# untitled.net
KiCad netlist of a schematic drawn in EAGLE
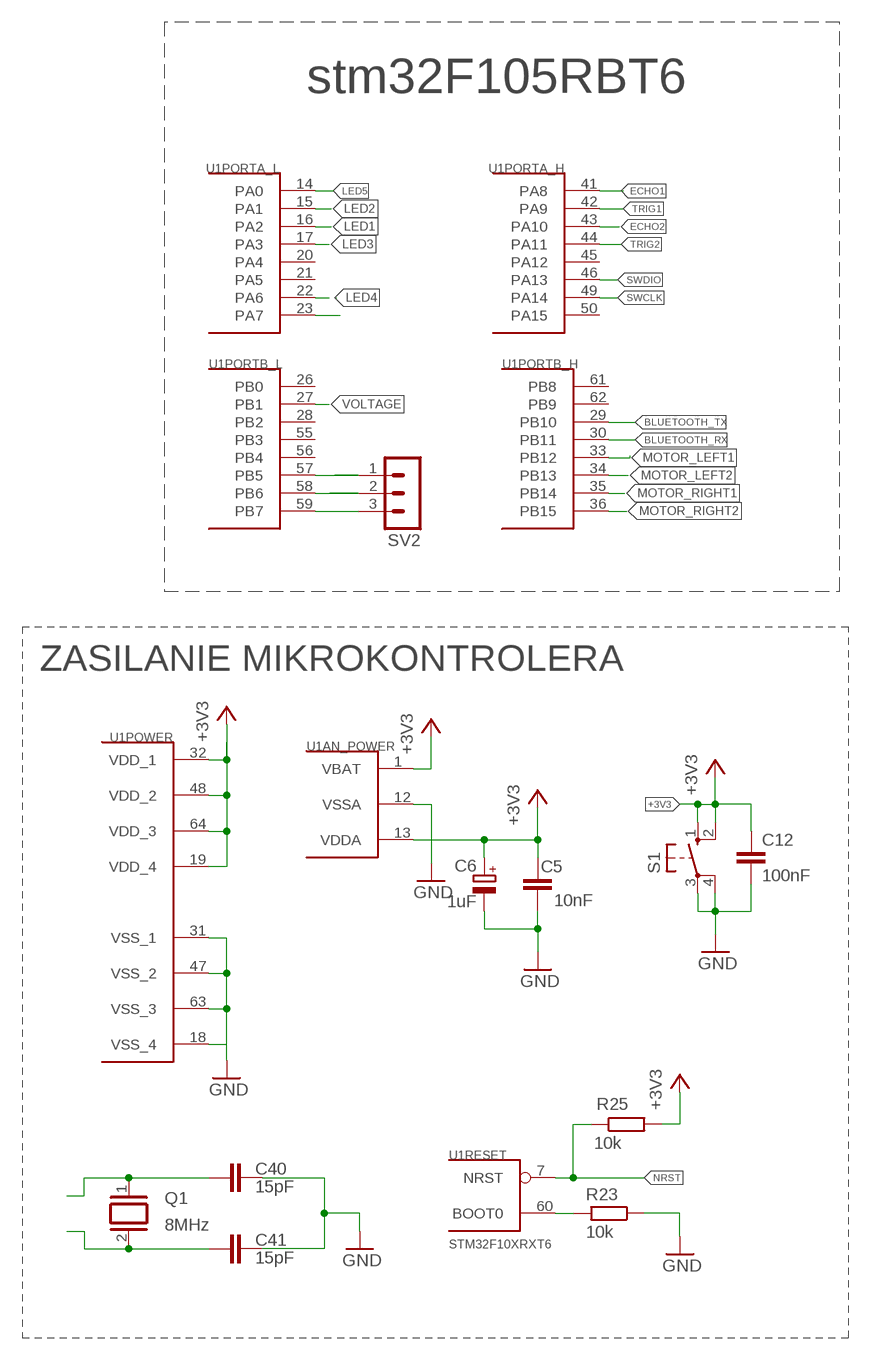
[diagram p0: schematic, sheet 1, part 1 of 2]
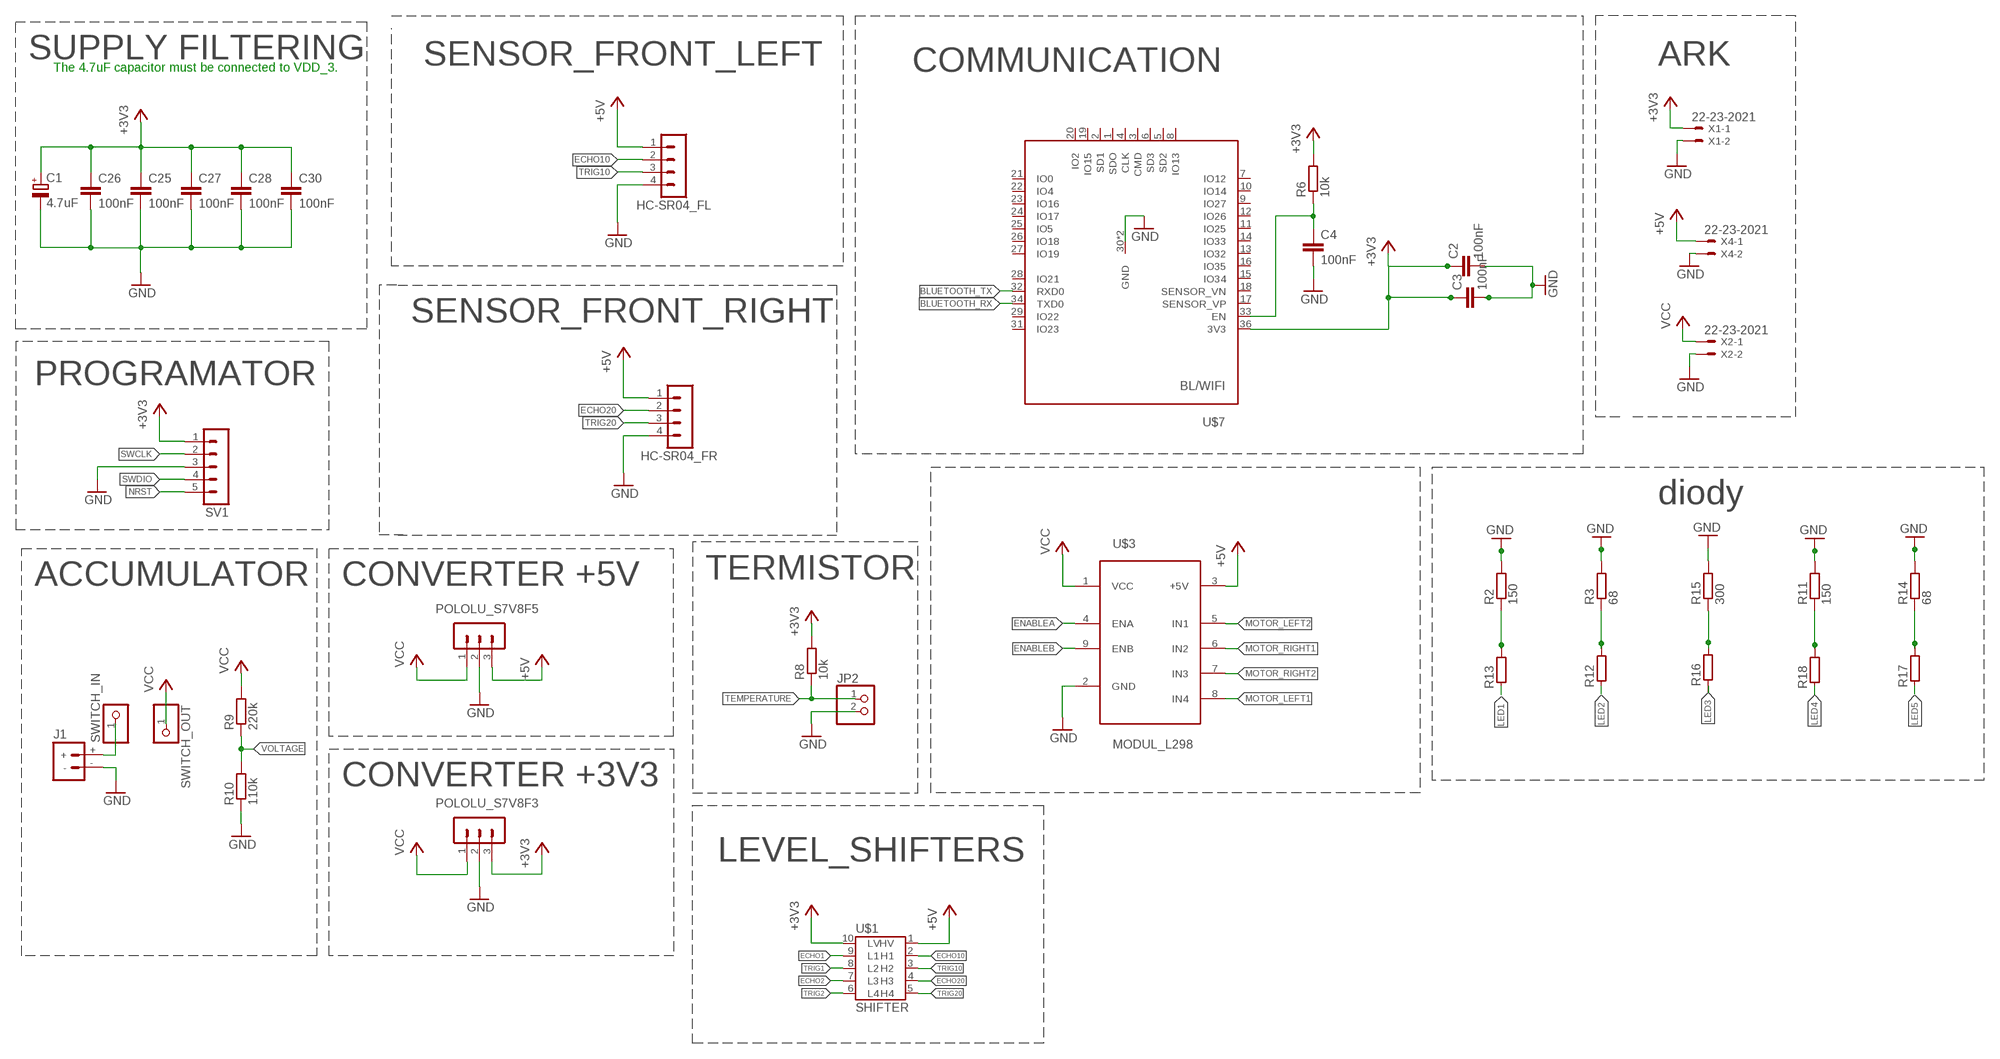
[diagram p1: schematic, sheet 1, part 2 of 2]

(export (version "E")
  (design (tool "Eeschema 10.0.6"))
  (components
    (comp (ref "C1")
      (value "4.7uF")
      (footprint "eagle-import:A_3216-18R")
      (libsource (lib "eagle-import") (part "CPOL-EUA/3216-18R"))
    )
    (comp (ref "C2")
      (value "100nF")
      (footprint "eagle-import:C0805")
      (libsource (lib "eagle-import") (part "C-EUC0805"))
    )
    (comp (ref "C3")
      (value "100nF")
      (footprint "eagle-import:C0805")
      (libsource (lib "eagle-import") (part "C-EUC0805"))
    )
    (comp (ref "C4")
      (value "100nF")
      (footprint "eagle-import:C0805")
      (libsource (lib "eagle-import") (part "C-EUC0805"))
    )
    (comp (ref "C5")
      (value "10nF")
      (footprint "eagle-import:C0805")
      (libsource (lib "eagle-import") (part "C-EUC0805"))
    )
    (comp (ref "C6")
      (value "1uF")
      (footprint "eagle-import:B_3528-21W")
      (libsource (lib "eagle-import") (part "CPOL-EUB/3528-21W"))
    )
    (comp (ref "C12")
      (value "100nF")
      (footprint "eagle-import:C0805")
      (libsource (lib "eagle-import") (part "C-EUC0805"))
    )
    (comp (ref "C25")
      (value "100nF")
      (footprint "eagle-import:C0805")
      (libsource (lib "eagle-import") (part "C-EUC0805"))
    )
    (comp (ref "C26")
      (value "100nF")
      (footprint "eagle-import:C0805")
      (libsource (lib "eagle-import") (part "C-EUC0805"))
    )
    (comp (ref "C27")
      (value "100nF")
      (footprint "eagle-import:C0805")
      (libsource (lib "eagle-import") (part "C-EUC0805"))
    )
    (comp (ref "C28")
      (value "100nF")
      (footprint "eagle-import:C0805")
      (libsource (lib "eagle-import") (part "C-EUC0805"))
    )
    (comp (ref "C30")
      (value "100nF")
      (footprint "eagle-import:C0805")
      (libsource (lib "eagle-import") (part "C-EUC0805"))
    )
    (comp (ref "C40")
      (value "15pF")
      (footprint "eagle-import:C0805")
      (libsource (lib "eagle-import") (part "C-EUC0805"))
    )
    (comp (ref "C41")
      (value "15pF")
      (footprint "eagle-import:C0805")
      (libsource (lib "eagle-import") (part "C-EUC0805"))
    )
    (comp (ref "HC-SR04_FL")
      (value "MA04-1")
      (footprint "eagle-import:MA04-1")
      (libsource (lib "eagle-import") (part "MA04-1"))
    )
    (comp (ref "HC-SR04_FR")
      (value "MA04-1")
      (footprint "eagle-import:MA04-1")
      (libsource (lib "eagle-import") (part "MA04-1"))
    )
    (comp (ref "J1")
      (value "BATTERY_CONN_DEANS")
      (footprint "eagle-import:DEANS")
      (libsource (lib "eagle-import") (part "BATTERY_CONN_DEANS"))
    )
    (comp (ref "JP2")
      (value "PINHD-1X2")
      (footprint "eagle-import:1X02")
      (libsource (lib "eagle-import") (part "PINHD-1X2"))
    )
    (comp (ref "POLOLU_S7V8F3")
      (value "MA03-1")
      (footprint "eagle-import:MA03-1")
      (libsource (lib "eagle-import") (part "MA03-1"))
    )
    (comp (ref "POLOLU_S7V8F5")
      (value "MA03-1")
      (footprint "eagle-import:MA03-1")
      (libsource (lib "eagle-import") (part "MA03-1"))
    )
    (comp (ref "Q1")
      (value "8MHz")
      (footprint "eagle-import:Q")
      (libsource (lib "eagle-import") (part "XTAL"))
    )
    (comp (ref "R2")
      (value "150")
      (footprint "eagle-import:R0805")
      (libsource (lib "eagle-import") (part "R-EU_R0805"))
    )
    (comp (ref "R3")
      (value "68")
      (footprint "eagle-import:M0805")
      (libsource (lib "eagle-import") (part "resistor_348_R-EU_M0805"))
    )
    (comp (ref "R6")
      (value "10k")
      (footprint "eagle-import:M0805")
      (libsource (lib "eagle-import") (part "resistor_348_R-EU_M0805"))
    )
    (comp (ref "R8")
      (value "10k")
      (footprint "eagle-import:R0805")
      (libsource (lib "eagle-import") (part "R-EU_R0805"))
    )
    (comp (ref "R9")
      (value "220k")
      (footprint "eagle-import:R0805")
      (libsource (lib "eagle-import") (part "R-EU_R0805"))
    )
    (comp (ref "R10")
      (value "110k")
      (footprint "eagle-import:R0805")
      (libsource (lib "eagle-import") (part "R-EU_R0805"))
    )
    (comp (ref "R11")
      (value "150")
      (footprint "eagle-import:R0805")
      (libsource (lib "eagle-import") (part "R-EU_R0805"))
    )
    (comp (ref "R12")
      (value "R-EU_0204/5")
      (footprint "eagle-import:0204_5")
      (libsource (lib "eagle-import") (part "R-EU_0204/5"))
    )
    (comp (ref "R13")
      (value "R-EU_0204/5")
      (footprint "eagle-import:0204_5")
      (libsource (lib "eagle-import") (part "R-EU_0204/5"))
    )
    (comp (ref "R14")
      (value "68")
      (footprint "eagle-import:M0805")
      (libsource (lib "eagle-import") (part "resistor_348_R-EU_M0805"))
    )
    (comp (ref "R15")
      (value "300")
      (footprint "eagle-import:R0805")
      (libsource (lib "eagle-import") (part "R-EU_R0805"))
    )
    (comp (ref "R16")
      (value "R-EU_0204/5")
      (footprint "eagle-import:0204_5")
      (libsource (lib "eagle-import") (part "R-EU_0204/5"))
    )
    (comp (ref "R17")
      (value "R-EU_0204/5")
      (footprint "eagle-import:0204_5")
      (libsource (lib "eagle-import") (part "R-EU_0204/5"))
    )
    (comp (ref "R18")
      (value "R-EU_0204/5")
      (footprint "eagle-import:0204_5")
      (libsource (lib "eagle-import") (part "R-EU_0204/5"))
    )
    (comp (ref "R23")
      (value "10k")
      (footprint "eagle-import:R0805")
      (libsource (lib "eagle-import") (part "R-EU_R0805"))
    )
    (comp (ref "R25")
      (value "10k")
      (footprint "eagle-import:R0805")
      (libsource (lib "eagle-import") (part "R-EU_R0805"))
    )
    (comp (ref "S1")
      (value "TACT_SWITCH")
      (footprint "eagle-import:B3F-10XX")
      (libsource (lib "eagle-import") (part "TACT_SWITCH"))
    )
    (comp (ref "SV1")
      (value "MA05-1")
      (footprint "eagle-import:MA05-1")
      (libsource (lib "eagle-import") (part "MA05-1"))
    )
    (comp (ref "SV2")
      (value "MA03-1")
      (footprint "eagle-import:MA03-1")
      (libsource (lib "eagle-import") (part "MA03-1"))
    )
    (comp (ref "SWITCH_IN")
      (value "PINHD-1X1")
      (footprint "eagle-import:1X01")
      (libsource (lib "eagle-import") (part "PINHD-1X1"))
    )
    (comp (ref "SWITCH_OUT")
      (value "PINHD-1X1")
      (footprint "eagle-import:1X01")
      (libsource (lib "eagle-import") (part "PINHD-1X1"))
    )
    (comp (ref "U$1")
      (value "SHIFTER")
      (footprint "eagle-import:SHIFTER")
      (libsource (lib "eagle-import") (part "SHIFTER"))
    )
    (comp (ref "U$3")
      (value "MODUL_L298")
      (footprint "eagle-import:MODUL_L298")
      (libsource (lib "eagle-import") (part "MODUL_L298"))
    )
    (comp (ref "U$7")
      (value "BL/WIFI")
      (footprint "eagle-import:BL_WIFI")
      (libsource (lib "eagle-import") (part "BL/WIFI"))
    )
    (comp (ref "U1")
      (value "STM32F10XRXT6")
      (footprint "eagle-import:TQFP64")
      (libsource (lib "eagle-import") (part "STM32F10XRXT6"))
    )
    (comp (ref "X1")
      (value "22-23-2021")
      (footprint "eagle-import:22-23-2021")
      (fields (field (name "MF") "MOLEX"))
      (libsource (lib "eagle-import") (part "22-23-2021"))
    )
    (comp (ref "X2")
      (value "22-23-2021")
      (footprint "eagle-import:22-23-2021")
      (fields (field (name "MF") "MOLEX"))
      (libsource (lib "eagle-import") (part "22-23-2021"))
    )
    (comp (ref "X4")
      (value "22-23-2021")
      (footprint "eagle-import:22-23-2021")
      (fields (field (name "MF") "MOLEX"))
      (libsource (lib "eagle-import") (part "22-23-2021"))
    )
  )
  (nets
    (net (code "1") (name "+3V3") (class "Default")
      (node (ref "C1") (pin "+") (pinfunction "+_+") (pintype "passive"))
      (node (ref "C12") (pin "1") (pinfunction "1_1") (pintype "passive"))
      (node (ref "C2") (pin "1") (pinfunction "1_1") (pintype "passive"))
      (node (ref "C25") (pin "1") (pinfunction "1_1") (pintype "passive"))
      (node (ref "C26") (pin "1") (pinfunction "1_1") (pintype "passive"))
      (node (ref "C27") (pin "1") (pinfunction "1_1") (pintype "passive"))
      (node (ref "C28") (pin "1") (pinfunction "1_1") (pintype "passive"))
      (node (ref "C3") (pin "1") (pinfunction "1_1") (pintype "passive"))
      (node (ref "C30") (pin "1") (pinfunction "1_1") (pintype "passive"))
      (node (ref "C5") (pin "2") (pinfunction "2_2") (pintype "passive"))
      (node (ref "C6") (pin "+") (pinfunction "+_+") (pintype "passive"))
      (node (ref "POLOLU_S7V8F3") (pin "3") (pinfunction "3_3") (pintype "passive"))
      (node (ref "R25") (pin "2") (pinfunction "2_2") (pintype "passive"))
      (node (ref "R6") (pin "2") (pinfunction "2_2") (pintype "passive"))
      (node (ref "R8") (pin "2") (pinfunction "2_2") (pintype "passive"))
      (node (ref "S1") (pin "1") (pinfunction "S_1") (pintype "passive"))
      (node (ref "S1") (pin "2") (pinfunction "S1_2") (pintype "passive"))
      (node (ref "SV1") (pin "1") (pinfunction "1_1") (pintype "passive"))
      (node (ref "U$1") (pin "10") (pinfunction "LV_10") (pintype "bidirectional"))
      (node (ref "U$7") (pin "36") (pinfunction "3V3_36") (pintype "bidirectional"))
      (node (ref "U1") (pin "1") (pinfunction "VBAT_1") (pintype "power_in"))
      (node (ref "U1") (pin "13") (pinfunction "VDDA_13") (pintype "power_in"))
      (node (ref "U1") (pin "19") (pinfunction "VDD_4_19") (pintype "power_in"))
      (node (ref "U1") (pin "32") (pinfunction "VDD_1_32") (pintype "power_in"))
      (node (ref "U1") (pin "48") (pinfunction "VDD_2_48") (pintype "power_in"))
      (node (ref "U1") (pin "64") (pinfunction "VDD_3_64") (pintype "power_in"))
      (node (ref "X1") (pin "1") (pinfunction "S_1") (pintype "passive"))
    )
    (net (code "2") (name "+5V") (class "Default")
      (node (ref "HC-SR04_FL") (pin "1") (pinfunction "1_1") (pintype "passive"))
      (node (ref "HC-SR04_FR") (pin "1") (pinfunction "1_1") (pintype "passive"))
      (node (ref "POLOLU_S7V8F5") (pin "3") (pinfunction "3_3") (pintype "passive"))
      (node (ref "U$1") (pin "1") (pinfunction "HV_1") (pintype "bidirectional"))
      (node (ref "U$3") (pin "3") (pinfunction "+5V_3") (pintype "bidirectional"))
      (node (ref "X4") (pin "1") (pinfunction "S_1") (pintype "passive"))
    )
    (net (code "3") (name "BLUETOOTH_RX") (class "Default")
      (node (ref "U$7") (pin "34") (pinfunction "TXD0_34") (pintype "bidirectional"))
      (node (ref "U1") (pin "30") (pinfunction "PB11_30") (pintype "bidirectional"))
    )
    (net (code "4") (name "BLUETOOTH_TX") (class "Default")
      (node (ref "U$7") (pin "32") (pinfunction "RXD0_32") (pintype "bidirectional"))
      (node (ref "U1") (pin "29") (pinfunction "PB10_29") (pintype "bidirectional"))
    )
    (net (code "5") (name "ECHO1") (class "Default")
      (node (ref "U$1") (pin "9") (pinfunction "L1_9") (pintype "bidirectional"))
      (node (ref "U1") (pin "41") (pinfunction "PA8_41") (pintype "bidirectional"))
    )
    (net (code "6") (name "ECHO2") (class "Default")
      (node (ref "U$1") (pin "7") (pinfunction "L3_7") (pintype "bidirectional"))
      (node (ref "U1") (pin "43") (pinfunction "PA10_43") (pintype "bidirectional"))
    )
    (net (code "7") (name "ECHO10") (class "Default")
      (node (ref "HC-SR04_FL") (pin "2") (pinfunction "2_2") (pintype "passive"))
      (node (ref "U$1") (pin "2") (pinfunction "H1_2") (pintype "bidirectional"))
    )
    (net (code "8") (name "ECHO20") (class "Default")
      (node (ref "HC-SR04_FR") (pin "2") (pinfunction "2_2") (pintype "passive"))
      (node (ref "U$1") (pin "4") (pinfunction "H3_4") (pintype "bidirectional"))
    )
    (net (code "9") (name "ENABLEA") (class "Default")
      (node (ref "U$3") (pin "4") (pinfunction "ENA_4") (pintype "bidirectional"))
    )
    (net (code "10") (name "ENABLEB") (class "Default")
      (node (ref "U$3") (pin "9") (pinfunction "ENB_9") (pintype "bidirectional"))
    )
    (net (code "11") (name "GND") (class "Default")
      (node (ref "C1") (pin "-") (pinfunction "-_-") (pintype "passive"))
      (node (ref "C12") (pin "2") (pinfunction "2_2") (pintype "passive"))
      (node (ref "C2") (pin "2") (pinfunction "2_2") (pintype "passive"))
      (node (ref "C25") (pin "2") (pinfunction "2_2") (pintype "passive"))
      (node (ref "C26") (pin "2") (pinfunction "2_2") (pintype "passive"))
      (node (ref "C27") (pin "2") (pinfunction "2_2") (pintype "passive"))
      (node (ref "C28") (pin "2") (pinfunction "2_2") (pintype "passive"))
      (node (ref "C3") (pin "2") (pinfunction "2_2") (pintype "passive"))
      (node (ref "C30") (pin "2") (pinfunction "2_2") (pintype "passive"))
      (node (ref "C4") (pin "2") (pinfunction "2_2") (pintype "passive"))
      (node (ref "C40") (pin "2") (pinfunction "2_2") (pintype "passive"))
      (node (ref "C41") (pin "2") (pinfunction "2_2") (pintype "passive"))
      (node (ref "C5") (pin "1") (pinfunction "1_1") (pintype "passive"))
      (node (ref "C6") (pin "-") (pinfunction "-_-") (pintype "passive"))
      (node (ref "HC-SR04_FL") (pin "4") (pinfunction "4_4") (pintype "passive"))
      (node (ref "HC-SR04_FR") (pin "4") (pinfunction "4_4") (pintype "passive"))
      (node (ref "J1") (pin "-") (pinfunction "-_-") (pintype "passive"))
      (node (ref "JP2") (pin "2") (pinfunction "2_2") (pintype "passive"))
      (node (ref "POLOLU_S7V8F3") (pin "2") (pinfunction "2_2") (pintype "passive"))
      (node (ref "POLOLU_S7V8F5") (pin "2") (pinfunction "2_2") (pintype "passive"))
      (node (ref "R10") (pin "1") (pinfunction "1_1") (pintype "passive"))
      (node (ref "R11") (pin "2") (pinfunction "2_2") (pintype "passive"))
      (node (ref "R14") (pin "2") (pinfunction "2_2") (pintype "passive"))
      (node (ref "R15") (pin "2") (pinfunction "2_2") (pintype "passive"))
      (node (ref "R2") (pin "2") (pinfunction "2_2") (pintype "passive"))
      (node (ref "R23") (pin "1") (pinfunction "1_1") (pintype "passive"))
      (node (ref "R3") (pin "2") (pinfunction "2_2") (pintype "passive"))
      (node (ref "S1") (pin "3") (pinfunction "P_3") (pintype "passive"))
      (node (ref "S1") (pin "4") (pinfunction "P1_4") (pintype "passive"))
      (node (ref "SV1") (pin "3") (pinfunction "3_3") (pintype "passive"))
      (node (ref "U$3") (pin "2") (pinfunction "GND_2") (pintype "bidirectional"))
      (node (ref "U$7") (pin "30") (pinfunction "GND_30") (pintype "bidirectional"))
      (node (ref "U$7") (pin "35") (pinfunction "GND_35") (pintype "bidirectional"))
      (node (ref "U1") (pin "12") (pinfunction "VSSA_12") (pintype "power_in"))
      (node (ref "U1") (pin "18") (pinfunction "VSS_4_18") (pintype "power_in"))
      (node (ref "U1") (pin "31") (pinfunction "VSS_1_31") (pintype "power_in"))
      (node (ref "U1") (pin "47") (pinfunction "VSS_2_47") (pintype "power_in"))
      (node (ref "U1") (pin "63") (pinfunction "VSS_3_63") (pintype "power_in"))
      (node (ref "X1") (pin "2") (pinfunction "S_2") (pintype "passive"))
      (node (ref "X2") (pin "2") (pinfunction "S_2") (pintype "passive"))
      (node (ref "X4") (pin "2") (pinfunction "S_2") (pintype "passive"))
    )
    (net (code "12") (name "LED1") (class "Default")
      (node (ref "R13") (pin "1") (pinfunction "1_1") (pintype "passive"))
      (node (ref "U1") (pin "16") (pinfunction "PA2_16") (pintype "bidirectional"))
    )
    (net (code "13") (name "LED2") (class "Default")
      (node (ref "R12") (pin "1") (pinfunction "1_1") (pintype "passive"))
      (node (ref "U1") (pin "15") (pinfunction "PA1_15") (pintype "bidirectional"))
    )
    (net (code "14") (name "LED3") (class "Default")
      (node (ref "R16") (pin "1") (pinfunction "1_1") (pintype "passive"))
      (node (ref "U1") (pin "17") (pinfunction "PA3_17") (pintype "bidirectional"))
    )
    (net (code "15") (name "LED4") (class "Default")
      (node (ref "R18") (pin "1") (pinfunction "1_1") (pintype "passive"))
      (node (ref "U1") (pin "22") (pinfunction "PA6_22") (pintype "bidirectional"))
    )
    (net (code "16") (name "LED5") (class "Default")
      (node (ref "R17") (pin "1") (pinfunction "1_1") (pintype "passive"))
      (node (ref "U1") (pin "14") (pinfunction "PA0_14") (pintype "bidirectional"))
    )
    (net (code "17") (name "MOTOR_LEFT1") (class "Default")
      (node (ref "U$3") (pin "8") (pinfunction "IN4_8") (pintype "bidirectional"))
      (node (ref "U1") (pin "33") (pinfunction "PB12_33") (pintype "bidirectional"))
    )
    (net (code "18") (name "MOTOR_LEFT2") (class "Default")
      (node (ref "U$3") (pin "5") (pinfunction "IN1_5") (pintype "bidirectional"))
      (node (ref "U1") (pin "34") (pinfunction "PB13_34") (pintype "bidirectional"))
    )
    (net (code "19") (name "MOTOR_RIGHT1") (class "Default")
      (node (ref "U$3") (pin "6") (pinfunction "IN2_6") (pintype "bidirectional"))
      (node (ref "U1") (pin "35") (pinfunction "PB14_35") (pintype "bidirectional"))
    )
    (net (code "20") (name "MOTOR_RIGHT2") (class "Default")
      (node (ref "U$3") (pin "7") (pinfunction "IN3_7") (pintype "bidirectional"))
      (node (ref "U1") (pin "36") (pinfunction "PB15_36") (pintype "bidirectional"))
    )
    (net (code "21") (name "NRST") (class "Default")
      (node (ref "R25") (pin "1") (pinfunction "1_1") (pintype "passive"))
      (node (ref "SV1") (pin "5") (pinfunction "5_5") (pintype "passive"))
      (node (ref "U1") (pin "7") (pinfunction "NRST_7") (pintype "input"))
    )
    (net (code "22") (name "Net-(C40-Pad1)") (class "Default")
      (node (ref "C40") (pin "1") (pinfunction "1_1") (pintype "passive"))
      (node (ref "Q1") (pin "1") (pinfunction "1_1") (pintype "passive"))
    )
    (net (code "23") (name "Net-(C41-Pad1)") (class "Default")
      (node (ref "C41") (pin "1") (pinfunction "1_1") (pintype "passive"))
      (node (ref "Q1") (pin "2") (pinfunction "2_2") (pintype "passive"))
    )
    (net (code "24") (name "Net-(J1-Pad+)") (class "Default")
      (node (ref "J1") (pin "+") (pinfunction "+_+") (pintype "passive"))
      (node (ref "SWITCH_IN") (pin "1") (pinfunction "1_1") (pintype "passive"))
    )
    (net (code "25") (name "Net-(R11-Pad1)") (class "Default")
      (node (ref "R11") (pin "1") (pinfunction "1_1") (pintype "passive"))
      (node (ref "R18") (pin "2") (pinfunction "2_2") (pintype "passive"))
    )
    (net (code "26") (name "Net-(R12-Pad2)") (class "Default")
      (node (ref "R12") (pin "2") (pinfunction "2_2") (pintype "passive"))
      (node (ref "R3") (pin "1") (pinfunction "1_1") (pintype "passive"))
    )
    (net (code "27") (name "Net-(R13-Pad2)") (class "Default")
      (node (ref "R13") (pin "2") (pinfunction "2_2") (pintype "passive"))
      (node (ref "R2") (pin "1") (pinfunction "1_1") (pintype "passive"))
    )
    (net (code "28") (name "Net-(R14-Pad1)") (class "Default")
      (node (ref "R14") (pin "1") (pinfunction "1_1") (pintype "passive"))
      (node (ref "R17") (pin "2") (pinfunction "2_2") (pintype "passive"))
    )
    (net (code "29") (name "Net-(R15-Pad1)") (class "Default")
      (node (ref "R15") (pin "1") (pinfunction "1_1") (pintype "passive"))
      (node (ref "R16") (pin "2") (pinfunction "2_2") (pintype "passive"))
    )
    (net (code "30") (name "Net-(U$7-EN)") (class "Default")
      (node (ref "C4") (pin "1") (pinfunction "1_1") (pintype "passive"))
      (node (ref "R6") (pin "1") (pinfunction "1_1") (pintype "passive"))
      (node (ref "U$7") (pin "33") (pinfunction "EN_33") (pintype "bidirectional"))
    )
    (net (code "31") (name "Net-(U1E-PB5)") (class "Default")
      (node (ref "SV2") (pin "1") (pinfunction "1_1") (pintype "passive"))
      (node (ref "U1") (pin "57") (pinfunction "PB5_57") (pintype "bidirectional"))
    )
    (net (code "32") (name "Net-(U1E-PB6)") (class "Default")
      (node (ref "SV2") (pin "2") (pinfunction "2_2") (pintype "passive"))
      (node (ref "U1") (pin "58") (pinfunction "PB6_58") (pintype "bidirectional"))
    )
    (net (code "33") (name "Net-(U1E-PB7)") (class "Default")
      (node (ref "SV2") (pin "3") (pinfunction "3_3") (pintype "passive"))
      (node (ref "U1") (pin "59") (pinfunction "PB7_59") (pintype "bidirectional"))
    )
    (net (code "34") (name "Net-(U1J-BOOT0)") (class "Default")
      (node (ref "R23") (pin "2") (pinfunction "2_2") (pintype "passive"))
      (node (ref "U1") (pin "60") (pinfunction "BOOT0_60") (pintype "input"))
    )
    (net (code "35") (name "SWCLK") (class "Default")
      (node (ref "SV1") (pin "2") (pinfunction "2_2") (pintype "passive"))
      (node (ref "U1") (pin "49") (pinfunction "PA14_49") (pintype "bidirectional"))
    )
    (net (code "36") (name "SWDIO") (class "Default")
      (node (ref "SV1") (pin "4") (pinfunction "4_4") (pintype "passive"))
      (node (ref "U1") (pin "46") (pinfunction "PA13_46") (pintype "bidirectional"))
    )
    (net (code "37") (name "TEMPERATURE") (class "Default")
      (node (ref "JP2") (pin "1") (pinfunction "1_1") (pintype "passive"))
      (node (ref "R8") (pin "1") (pinfunction "1_1") (pintype "passive"))
    )
    (net (code "38") (name "TRIG1") (class "Default")
      (node (ref "U$1") (pin "8") (pinfunction "L2_8") (pintype "bidirectional"))
      (node (ref "U1") (pin "42") (pinfunction "PA9_42") (pintype "bidirectional"))
    )
    (net (code "39") (name "TRIG2") (class "Default")
      (node (ref "U$1") (pin "6") (pinfunction "L4_6") (pintype "bidirectional"))
      (node (ref "U1") (pin "44") (pinfunction "PA11_44") (pintype "bidirectional"))
    )
    (net (code "40") (name "TRIG10") (class "Default")
      (node (ref "HC-SR04_FL") (pin "3") (pinfunction "3_3") (pintype "passive"))
      (node (ref "U$1") (pin "3") (pinfunction "H2_3") (pintype "bidirectional"))
    )
    (net (code "41") (name "TRIG20") (class "Default")
      (node (ref "HC-SR04_FR") (pin "3") (pinfunction "3_3") (pintype "passive"))
      (node (ref "U$1") (pin "5") (pinfunction "H4_5") (pintype "bidirectional"))
    )
    (net (code "42") (name "VCC") (class "Default")
      (node (ref "POLOLU_S7V8F3") (pin "1") (pinfunction "1_1") (pintype "passive"))
      (node (ref "POLOLU_S7V8F5") (pin "1") (pinfunction "1_1") (pintype "passive"))
      (node (ref "R9") (pin "2") (pinfunction "2_2") (pintype "passive"))
      (node (ref "SWITCH_OUT") (pin "1") (pinfunction "1_1") (pintype "passive"))
      (node (ref "U$3") (pin "1") (pinfunction "VCC_1") (pintype "bidirectional"))
      (node (ref "X2") (pin "1") (pinfunction "S_1") (pintype "passive"))
    )
    (net (code "43") (name "VOLTAGE") (class "Default")
      (node (ref "R10") (pin "2") (pinfunction "2_2") (pintype "passive"))
      (node (ref "R9") (pin "1") (pinfunction "1_1") (pintype "passive"))
      (node (ref "U1") (pin "27") (pinfunction "PB1_27") (pintype "bidirectional"))
    )
    (net (code "44") (name "unconnected-(U$7-CLK-Pad4)") (class "Default")
      (node (ref "U$7") (pin "4") (pinfunction "CLK_4") (pintype "bidirectional"))
    )
    (net (code "45") (name "unconnected-(U$7-CMD-Pad3)") (class "Default")
      (node (ref "U$7") (pin "3") (pinfunction "CMD_3") (pintype "bidirectional"))
    )
    (net (code "46") (name "unconnected-(U$7-IO0-Pad21)") (class "Default")
      (node (ref "U$7") (pin "21") (pinfunction "IO0_21") (pintype "bidirectional"))
    )
    (net (code "47") (name "unconnected-(U$7-IO2-Pad20)") (class "Default")
      (node (ref "U$7") (pin "20") (pinfunction "IO2_20") (pintype "bidirectional"))
    )
    (net (code "48") (name "unconnected-(U$7-IO4-Pad22)") (class "Default")
      (node (ref "U$7") (pin "22") (pinfunction "IO4_22") (pintype "bidirectional"))
    )
    (net (code "49") (name "unconnected-(U$7-IO5-Pad25)") (class "Default")
      (node (ref "U$7") (pin "25") (pinfunction "IO5_25") (pintype "bidirectional"))
    )
    (net (code "50") (name "unconnected-(U$7-IO12-Pad7)") (class "Default")
      (node (ref "U$7") (pin "7") (pinfunction "IO12_7") (pintype "bidirectional"))
    )
    (net (code "51") (name "unconnected-(U$7-IO13-Pad8)") (class "Default")
      (node (ref "U$7") (pin "8") (pinfunction "IO13_8") (pintype "bidirectional"))
    )
    (net (code "52") (name "unconnected-(U$7-IO14-Pad10)") (class "Default")
      (node (ref "U$7") (pin "10") (pinfunction "IO14_10") (pintype "bidirectional"))
    )
    (net (code "53") (name "unconnected-(U$7-IO15-Pad19)") (class "Default")
      (node (ref "U$7") (pin "19") (pinfunction "IO15_19") (pintype "bidirectional"))
    )
    (net (code "54") (name "unconnected-(U$7-IO16-Pad23)") (class "Default")
      (node (ref "U$7") (pin "23") (pinfunction "IO16_23") (pintype "bidirectional"))
    )
    (net (code "55") (name "unconnected-(U$7-IO17-Pad24)") (class "Default")
      (node (ref "U$7") (pin "24") (pinfunction "IO17_24") (pintype "bidirectional"))
    )
    (net (code "56") (name "unconnected-(U$7-IO18-Pad26)") (class "Default")
      (node (ref "U$7") (pin "26") (pinfunction "IO18_26") (pintype "bidirectional"))
    )
    (net (code "57") (name "unconnected-(U$7-IO19-Pad27)") (class "Default")
      (node (ref "U$7") (pin "27") (pinfunction "IO19_27") (pintype "bidirectional"))
    )
    (net (code "58") (name "unconnected-(U$7-IO21-Pad28)") (class "Default")
      (node (ref "U$7") (pin "28") (pinfunction "IO21_28") (pintype "bidirectional"))
    )
    (net (code "59") (name "unconnected-(U$7-IO22-Pad29)") (class "Default")
      (node (ref "U$7") (pin "29") (pinfunction "IO22_29") (pintype "bidirectional"))
    )
    (net (code "60") (name "unconnected-(U$7-IO23-Pad31)") (class "Default")
      (node (ref "U$7") (pin "31") (pinfunction "IO23_31") (pintype "bidirectional"))
    )
    (net (code "61") (name "unconnected-(U$7-IO25-Pad11)") (class "Default")
      (node (ref "U$7") (pin "11") (pinfunction "IO25_11") (pintype "bidirectional"))
    )
    (net (code "62") (name "unconnected-(U$7-IO26-Pad12)") (class "Default")
      (node (ref "U$7") (pin "12") (pinfunction "IO26_12") (pintype "bidirectional"))
    )
    (net (code "63") (name "unconnected-(U$7-IO27-Pad9)") (class "Default")
      (node (ref "U$7") (pin "9") (pinfunction "IO27_9") (pintype "bidirectional"))
    )
    (net (code "64") (name "unconnected-(U$7-IO32-Pad13)") (class "Default")
      (node (ref "U$7") (pin "13") (pinfunction "IO32_13") (pintype "bidirectional"))
    )
    (net (code "65") (name "unconnected-(U$7-IO33-Pad14)") (class "Default")
      (node (ref "U$7") (pin "14") (pinfunction "IO33_14") (pintype "bidirectional"))
    )
    (net (code "66") (name "unconnected-(U$7-IO34-Pad15)") (class "Default")
      (node (ref "U$7") (pin "15") (pinfunction "IO34_15") (pintype "bidirectional"))
    )
    (net (code "67") (name "unconnected-(U$7-IO35-Pad16)") (class "Default")
      (node (ref "U$7") (pin "16") (pinfunction "IO35_16") (pintype "bidirectional"))
    )
    (net (code "68") (name "unconnected-(U$7-SD1-Pad2)") (class "Default")
      (node (ref "U$7") (pin "2") (pinfunction "SD1_2") (pintype "bidirectional"))
    )
    (net (code "69") (name "unconnected-(U$7-SD2-Pad5)") (class "Default")
      (node (ref "U$7") (pin "5") (pinfunction "SD2_5") (pintype "bidirectional"))
    )
    (net (code "70") (name "unconnected-(U$7-SD3-Pad6)") (class "Default")
      (node (ref "U$7") (pin "6") (pinfunction "SD3_6") (pintype "bidirectional"))
    )
    (net (code "71") (name "unconnected-(U$7-SDO-Pad1)") (class "Default")
      (node (ref "U$7") (pin "1") (pinfunction "SDO_1") (pintype "bidirectional"))
    )
    (net (code "72") (name "unconnected-(U$7-SENSOR_VN-Pad18)") (class "Default")
      (node (ref "U$7") (pin "18") (pinfunction "SENSOR_VN_18") (pintype "bidirectional"))
    )
    (net (code "73") (name "unconnected-(U$7-SENSOR_VP-Pad17)") (class "Default")
      (node (ref "U$7") (pin "17") (pinfunction "SENSOR_VP_17") (pintype "bidirectional"))
    )
    (net (code "74") (name "unconnected-(U1B-PA12-Pad45)") (class "Default")
      (node (ref "U1") (pin "45") (pinfunction "PA12_45") (pintype "bidirectional"))
    )
    (net (code "75") (name "unconnected-(U1B-PA15-Pad50)") (class "Default")
      (node (ref "U1") (pin "50") (pinfunction "PA15_50") (pintype "bidirectional"))
    )
    (net (code "76") (name "unconnected-(U1C-PA4-Pad20)") (class "Default")
      (node (ref "U1") (pin "20") (pinfunction "PA4_20") (pintype "bidirectional"))
    )
    (net (code "77") (name "unconnected-(U1C-PA5-Pad21)") (class "Default")
      (node (ref "U1") (pin "21") (pinfunction "PA5_21") (pintype "bidirectional"))
    )
    (net (code "78") (name "unconnected-(U1C-PA7-Pad23)") (class "Default")
      (node (ref "U1") (pin "23") (pinfunction "PA7_23") (pintype "bidirectional"))
    )
    (net (code "79") (name "unconnected-(U1D-PB8-Pad61)") (class "Default")
      (node (ref "U1") (pin "61") (pinfunction "PB8_61") (pintype "bidirectional"))
    )
    (net (code "80") (name "unconnected-(U1D-PB9-Pad62)") (class "Default")
      (node (ref "U1") (pin "62") (pinfunction "PB9_62") (pintype "bidirectional"))
    )
    (net (code "81") (name "unconnected-(U1E-PB0-Pad26)") (class "Default")
      (node (ref "U1") (pin "26") (pinfunction "PB0_26") (pintype "bidirectional"))
    )
    (net (code "82") (name "unconnected-(U1E-PB2-Pad28)") (class "Default")
      (node (ref "U1") (pin "28") (pinfunction "PB2_28") (pintype "bidirectional"))
    )
    (net (code "83") (name "unconnected-(U1E-PB3-Pad55)") (class "Default")
      (node (ref "U1") (pin "55") (pinfunction "PB3_55") (pintype "bidirectional"))
    )
    (net (code "84") (name "unconnected-(U1E-PB4-Pad56)") (class "Default")
      (node (ref "U1") (pin "56") (pinfunction "PB4_56") (pintype "bidirectional"))
    )
  )
)
